# spider_mx8_2side_serial.net
KiCad netlist of a schematic drawn in EAGLE
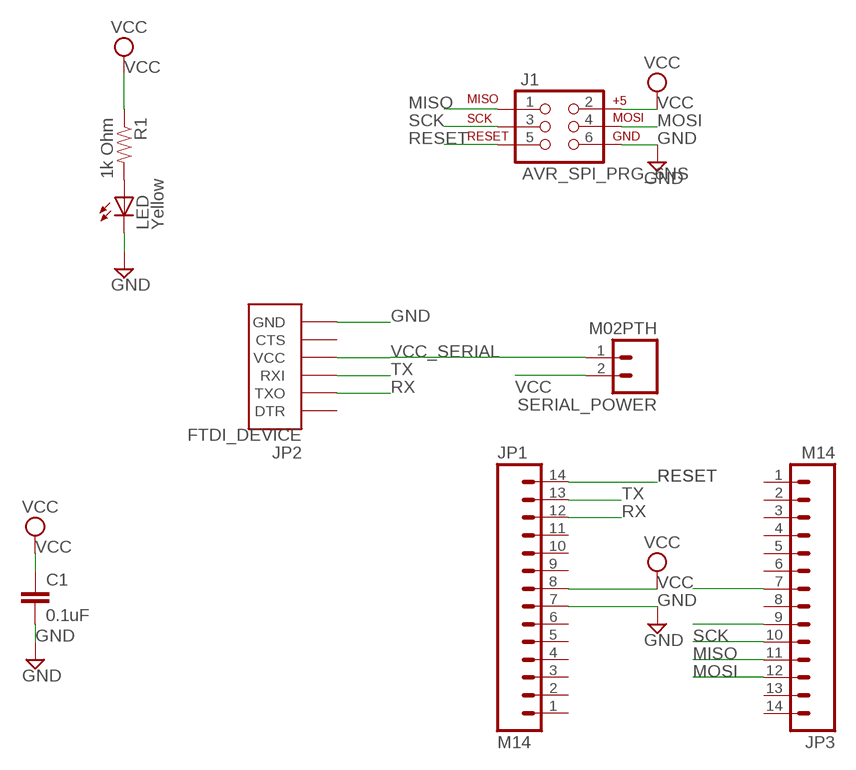
[diagram p0: schematic, sheet 1]

(export (version "E")
  (design (tool "Eeschema 10.0.6"))
  (components
    (comp (ref "C1")
      (value "0.1uF")
      (footprint "eagle-import:1206")
      (libsource (lib "eagle-import") (part "CAP1206"))
    )
    (comp (ref "J1")
      (value "AVR_SPI_PRG_6NS")
      (footprint "eagle-import:2X3-NS")
      (libsource (lib "eagle-import") (part "AVR_SPI_PRG_6NS"))
    )
    (comp (ref "JP1")
      (value "M14")
      (footprint "eagle-import:1X14")
      (libsource (lib "eagle-import") (part "M14"))
    )
    (comp (ref "JP2")
      (value "FTDI_DEVICE")
      (footprint "eagle-import:FTDI_DEVICE_SIDE")
      (libsource (lib "eagle-import") (part "FTDI_DEVICE"))
    )
    (comp (ref "JP3")
      (value "M14")
      (footprint "eagle-import:1X14")
      (libsource (lib "eagle-import") (part "M14"))
    )
    (comp (ref "LED")
      (value "Yellow")
      (footprint "eagle-import:LED-1206")
      (libsource (lib "eagle-import") (part "LED-YELLOWLILYPAD"))
    )
    (comp (ref "R1")
      (value "1k Ohm")
      (footprint "eagle-import:1206")
      (libsource (lib "eagle-import") (part "RESISTOR1206"))
    )
    (comp (ref "SERIAL_POWER")
      (value "M02PTH")
      (footprint "eagle-import:1X02")
      (libsource (lib "eagle-import") (part "M02PTH"))
    )
  )
  (nets
    (net (code "1") (name "/MISO") (class "Default")
      (node (ref "J1") (pin "1") (pinfunction "1_1") (pintype "passive"))
      (node (ref "JP3") (pin "11") (pinfunction "11_11") (pintype "passive"))
    )
    (net (code "2") (name "/MOSI") (class "Default")
      (node (ref "J1") (pin "4") (pinfunction "4_4") (pintype "passive"))
      (node (ref "JP3") (pin "12") (pinfunction "12_12") (pintype "passive"))
    )
    (net (code "3") (name "/RESET") (class "Default")
      (node (ref "J1") (pin "5") (pinfunction "5_5") (pintype "passive"))
      (node (ref "JP1") (pin "14") (pinfunction "14_14") (pintype "passive"))
    )
    (net (code "4") (name "/RX") (class "Default")
      (node (ref "JP1") (pin "12") (pinfunction "12_12") (pintype "passive"))
      (node (ref "JP2") (pin "P$2") (pinfunction "TXO_P$2") (pintype "bidirectional"))
    )
    (net (code "5") (name "/SCK") (class "Default")
      (node (ref "J1") (pin "3") (pinfunction "3_3") (pintype "passive"))
      (node (ref "JP3") (pin "10") (pinfunction "10_10") (pintype "passive"))
    )
    (net (code "6") (name "/TX") (class "Default")
      (node (ref "JP1") (pin "13") (pinfunction "13_13") (pintype "passive"))
      (node (ref "JP2") (pin "P$3") (pinfunction "RXI_P$3") (pintype "bidirectional"))
    )
    (net (code "7") (name "/VCC_SERIAL") (class "Default")
      (node (ref "JP2") (pin "P$4") (pinfunction "VCC_P$4") (pintype "bidirectional"))
      (node (ref "SERIAL_POWER") (pin "1") (pinfunction "1_1") (pintype "passive"))
    )
    (net (code "8") (name "GND") (class "Default")
      (node (ref "C1") (pin "2") (pinfunction "2_2") (pintype "passive"))
      (node (ref "J1") (pin "6") (pinfunction "6_6") (pintype "passive"))
      (node (ref "JP1") (pin "7") (pinfunction "7_7") (pintype "passive"))
      (node (ref "JP2") (pin "P$6") (pinfunction "GND_P$6") (pintype "bidirectional"))
      (node (ref "JP3") (pin "7") (pinfunction "7_7") (pintype "passive"))
      (node (ref "LED") (pin "C") (pinfunction "C_C") (pintype "passive"))
    )
    (net (code "9") (name "Net-(LED-PadA)") (class "Default")
      (node (ref "LED") (pin "A") (pinfunction "A_A") (pintype "passive"))
      (node (ref "R1") (pin "2") (pinfunction "2_2") (pintype "passive"))
    )
    (net (code "10") (name "VCC") (class "Default")
      (node (ref "C1") (pin "1") (pinfunction "1_1") (pintype "passive"))
      (node (ref "J1") (pin "2") (pinfunction "2_2") (pintype "passive"))
      (node (ref "JP1") (pin "8") (pinfunction "8_8") (pintype "passive"))
      (node (ref "JP3") (pin "9") (pinfunction "9_9") (pintype "passive"))
      (node (ref "R1") (pin "1") (pinfunction "1_1") (pintype "passive"))
      (node (ref "SERIAL_POWER") (pin "2") (pinfunction "2_2") (pintype "passive"))
    )
    (net (code "11") (name "unconnected-(JP1-Pad1)") (class "Default")
      (node (ref "JP1") (pin "1") (pinfunction "1_1") (pintype "passive"))
    )
    (net (code "12") (name "unconnected-(JP1-Pad2)") (class "Default")
      (node (ref "JP1") (pin "2") (pinfunction "2_2") (pintype "passive"))
    )
    (net (code "13") (name "unconnected-(JP1-Pad3)") (class "Default")
      (node (ref "JP1") (pin "3") (pinfunction "3_3") (pintype "passive"))
    )
    (net (code "14") (name "unconnected-(JP1-Pad4)") (class "Default")
      (node (ref "JP1") (pin "4") (pinfunction "4_4") (pintype "passive"))
    )
    (net (code "15") (name "unconnected-(JP1-Pad5)") (class "Default")
      (node (ref "JP1") (pin "5") (pinfunction "5_5") (pintype "passive"))
    )
    (net (code "16") (name "unconnected-(JP1-Pad6)") (class "Default")
      (node (ref "JP1") (pin "6") (pinfunction "6_6") (pintype "passive"))
    )
    (net (code "17") (name "unconnected-(JP1-Pad9)") (class "Default")
      (node (ref "JP1") (pin "9") (pinfunction "9_9") (pintype "passive"))
    )
    (net (code "18") (name "unconnected-(JP1-Pad10)") (class "Default")
      (node (ref "JP1") (pin "10") (pinfunction "10_10") (pintype "passive"))
    )
    (net (code "19") (name "unconnected-(JP1-Pad11)") (class "Default")
      (node (ref "JP1") (pin "11") (pinfunction "11_11") (pintype "passive"))
    )
    (net (code "20") (name "unconnected-(JP2-CTS-PadP$5)") (class "Default")
      (node (ref "JP2") (pin "P$5") (pinfunction "CTS_P$5") (pintype "bidirectional"))
    )
    (net (code "21") (name "unconnected-(JP2-DTR-PadP$1)") (class "Default")
      (node (ref "JP2") (pin "P$1") (pinfunction "DTR_P$1") (pintype "bidirectional"))
    )
    (net (code "22") (name "unconnected-(JP3-Pad1)") (class "Default")
      (node (ref "JP3") (pin "1") (pinfunction "1_1") (pintype "passive"))
    )
    (net (code "23") (name "unconnected-(JP3-Pad2)") (class "Default")
      (node (ref "JP3") (pin "2") (pinfunction "2_2") (pintype "passive"))
    )
    (net (code "24") (name "unconnected-(JP3-Pad3)") (class "Default")
      (node (ref "JP3") (pin "3") (pinfunction "3_3") (pintype "passive"))
    )
    (net (code "25") (name "unconnected-(JP3-Pad4)") (class "Default")
      (node (ref "JP3") (pin "4") (pinfunction "4_4") (pintype "passive"))
    )
    (net (code "26") (name "unconnected-(JP3-Pad5)") (class "Default")
      (node (ref "JP3") (pin "5") (pinfunction "5_5") (pintype "passive"))
    )
    (net (code "27") (name "unconnected-(JP3-Pad6)") (class "Default")
      (node (ref "JP3") (pin "6") (pinfunction "6_6") (pintype "passive"))
    )
    (net (code "28") (name "unconnected-(JP3-Pad8)") (class "Default")
      (node (ref "JP3") (pin "8") (pinfunction "8_8") (pintype "passive"))
    )
    (net (code "29") (name "unconnected-(JP3-Pad13)") (class "Default")
      (node (ref "JP3") (pin "13") (pinfunction "13_13") (pintype "passive"))
    )
    (net (code "30") (name "unconnected-(JP3-Pad14)") (class "Default")
      (node (ref "JP3") (pin "14") (pinfunction "14_14") (pintype "passive"))
    )
  )
)
